# OvercurrentDetectionLogic.net
KiCad netlist of a schematic drawn in Altium Designer
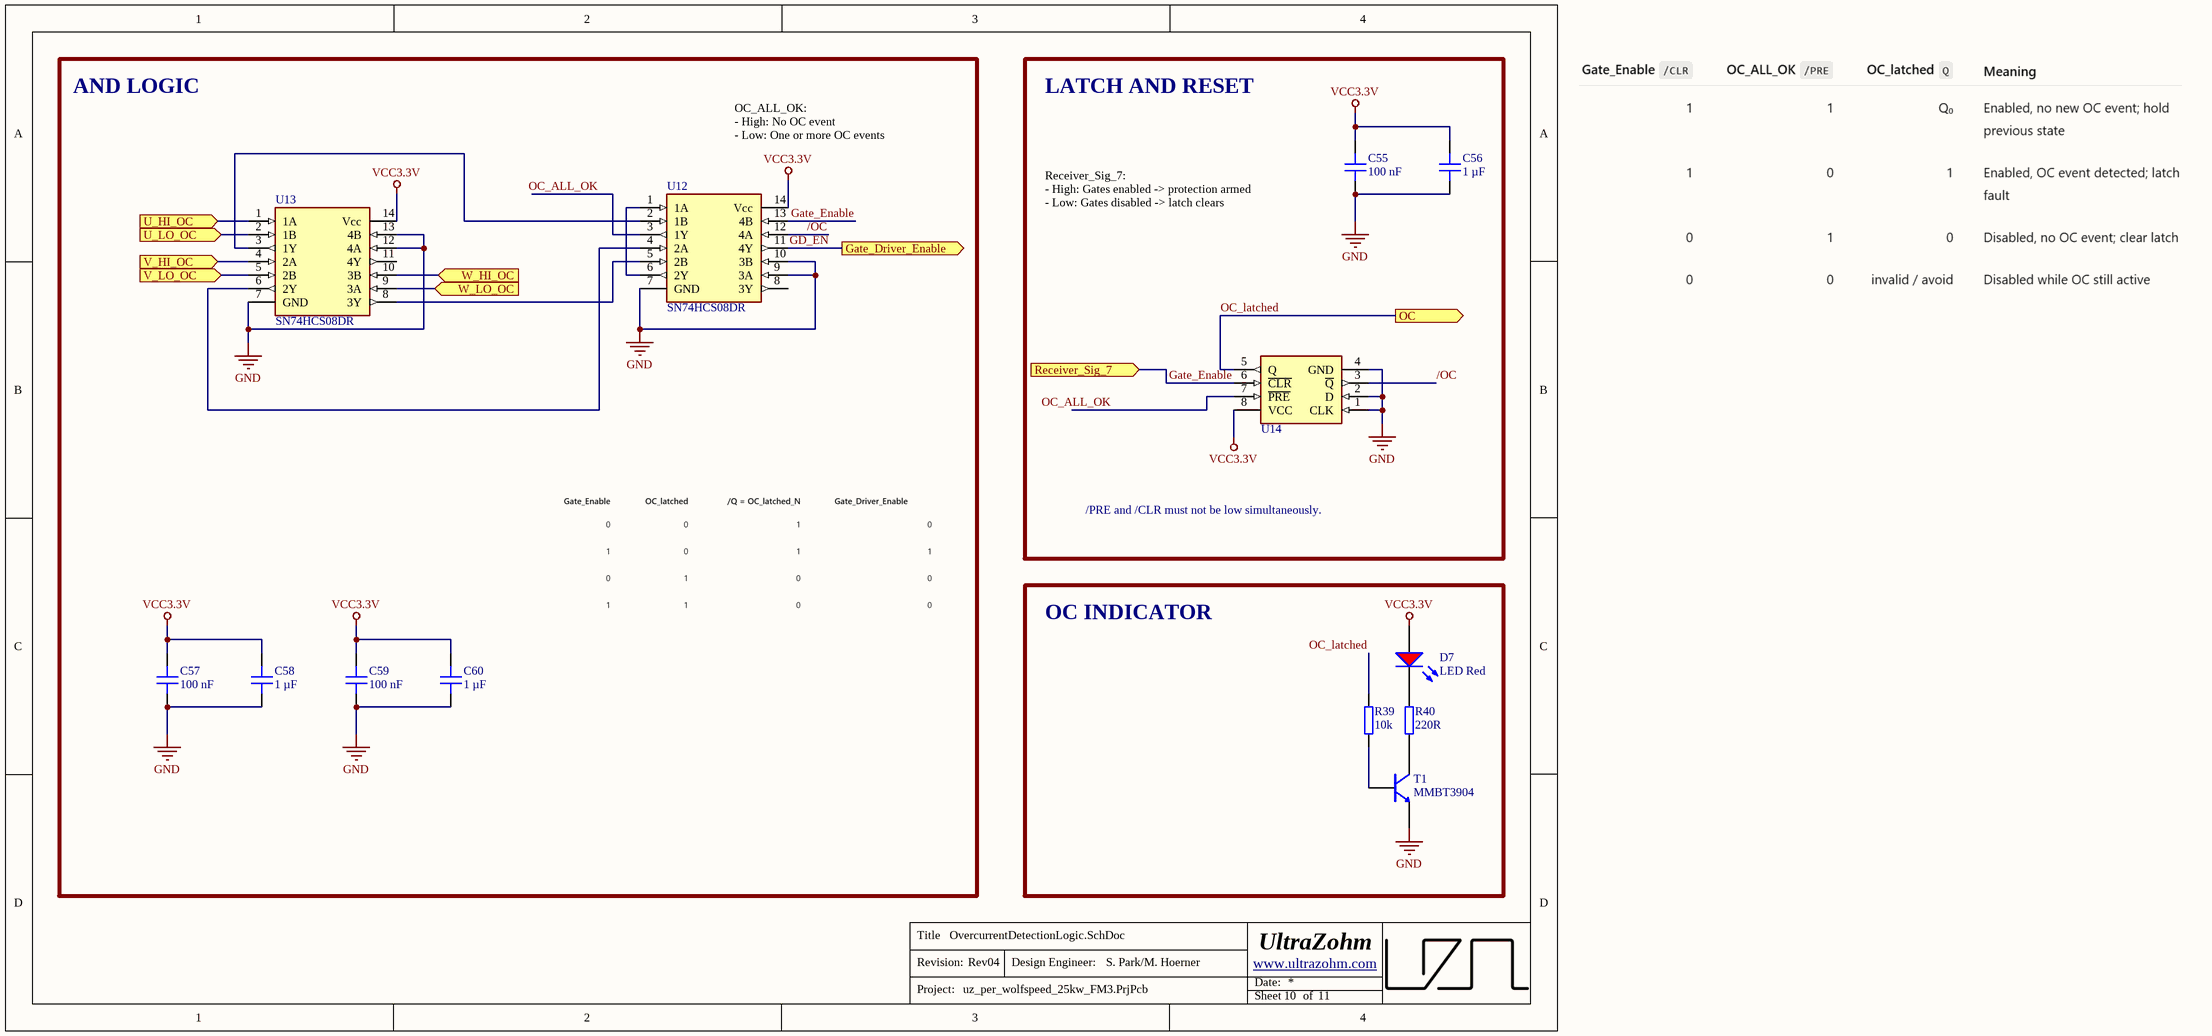
[diagram p0: OvercurrentDetectionLogic.SchDoc]

(export (version "E")
  (design (tool "Eeschema 10.0.6"))
  (components
    (comp (ref "C55")
      (value "100 nF")
      (footprint "C_0603")
      (description "Capacitor 0603, 50 VDC, 100nF, X7R")
      (fields
        (field (name "MANUFACTURER PART NUMBER") "C0603C104K5RAC3121")
        (field (name "MANUFACTURER") "KEMET")
        (field (name "CREATED FROM") "DHufnagel")
      )
      (libsource (lib "user") (part "Capacitor"))
    )
    (comp (ref "C56")
      (value "1 µF")
      (footprint "C_0603")
      (description "Capacitor 0603, 25 VDC, 1 µF, X7R")
      (fields
        (field (name "MANUFACTURER PART NUMBER") "C0603C105K3RAC7411")
        (field (name "MANUFACTURER") "KEMET")
        (field (name "CREATED FROM") "MGremer")
      )
      (libsource (lib "user") (part "Capacitor"))
    )
    (comp (ref "C57")
      (value "100 nF")
      (footprint "C_0603")
      (description "Capacitor 0603, 50 VDC, 100nF, X7R")
      (fields
        (field (name "MANUFACTURER PART NUMBER") "C0603C104K5RAC3121")
        (field (name "MANUFACTURER") "KEMET")
        (field (name "CREATED FROM") "DHufnagel")
      )
      (libsource (lib "user") (part "Capacitor"))
    )
    (comp (ref "C58")
      (value "1 µF")
      (footprint "C_0603")
      (description "Capacitor 0603, 25 VDC, 1 µF, X7R")
      (fields
        (field (name "MANUFACTURER PART NUMBER") "C0603C105K3RAC7411")
        (field (name "MANUFACTURER") "KEMET")
        (field (name "CREATED FROM") "MGremer")
      )
      (libsource (lib "user") (part "Capacitor"))
    )
    (comp (ref "C59")
      (value "100 nF")
      (footprint "C_0603")
      (description "Capacitor 0603, 50 VDC, 100nF, X7R")
      (fields
        (field (name "MANUFACTURER PART NUMBER") "C0603C104K5RAC3121")
        (field (name "MANUFACTURER") "KEMET")
        (field (name "CREATED FROM") "DHufnagel")
      )
      (libsource (lib "user") (part "Capacitor"))
    )
    (comp (ref "C60")
      (value "1 µF")
      (footprint "C_0603")
      (description "Capacitor 0603, 25 VDC, 1 µF, X7R")
      (fields
        (field (name "MANUFACTURER PART NUMBER") "C0603C105K3RAC7411")
        (field (name "MANUFACTURER") "KEMET")
        (field (name "CREATED FROM") "MGremer")
      )
      (libsource (lib "user") (part "Capacitor"))
    )
    (comp (ref "D7")
      (value "LED Red")
      (footprint "LEDM2012X80N")
      (description "Standard LEDs - SMD 0805 red")
      (fields
        (field (name "MANUFACTURER PART NUMBER") "UZgen_LED_0805_Red")
        (field (name "MANUFACTURER") "UZgen")
        (field (name "CREATED FROM") "UZgenTool")
      )
      (libsource (lib "user") (part "LED_Red"))
    )
    (comp (ref "R39")
      (value "10k")
      (footprint "RES 0603_1608")
      (description "SMD resistor E24 series")
      (fields
        (field (name "MANUFACTURER PART NUMBER") "RK73B1JTTD103J")
        (field (name "MANUFACTURER") "KOA Speer")
        (field (name "CREATED FROM") "MGremer")
      )
      (libsource (lib "user") (part "Resistor"))
    )
    (comp (ref "R40")
      (value "220R")
      (footprint "RES 0603_1608")
      (description "SMD resistor E24 series")
      (fields
        (field (name "MANUFACTURER PART NUMBER") "RK73B1JTTDD221J")
        (field (name "MANUFACTURER") "KOA Speer")
        (field (name "CREATED FROM") "MGremer")
      )
      (libsource (lib "user") (part "Resistor"))
    )
    (comp (ref "T1")
      (value "MMBT3904")
      (footprint "SOT95P280X145-3N")
      (fields
        (field (name "MANUFACTURER") "Jiangsu Changjing Electronics Technology Co., Ltd.")
        (field (name "LCSC PART NUMBER") "C20526")
        (field (name "CREATED FROM") "NDiringer")
      )
      (libsource (lib "user") (part "NPN-SOT23"))
    )
    (comp (ref "U12")
      (value "SN74HCS08DR")
      (footprint "SOIC127P600X175-14N")
      (description "Logische Gatter 4-ch 2-input 2-V to 6-V high-speed")
      (fields
        (field (name "MANUFACTURER") "Texas Instruments")
        (field (name "LCSC PART NUMBER") "C2868021")
        (field (name "CREATED FROM") "FRosner")
      )
      (libsource (lib "user") (part "SN74HCS32PWR"))
    )
    (comp (ref "U13")
      (value "SN74HCS08DR")
      (footprint "SOIC127P600X175-14N")
      (description "Logische Gatter 4-ch 2-input 2-V to 6-V high-speed")
      (fields
        (field (name "MANUFACTURER") "Texas Instruments")
        (field (name "LCSC PART NUMBER") "C2868021")
        (field (name "CREATED FROM") "FRosner")
      )
      (libsource (lib "user") (part "SN74HCS32PWR"))
    )
    (comp (ref "U14")
      (value "SN74LVC1G74DCTR")
      (footprint "MSOP-8")
      (description "Single Positive-Edge-Triggered D-Type Flip-Flop with Clear and Preset")
      (fields
        (field (name "MANUFACTURER") "Texas Instruments")
        (field (name "LCSC PART NUMBER") "C840104")
        (field (name "CREATED FROM") "FRosner")
      )
      (libsource (lib "user") (part "SN74LVC1G74DCTR"))
    )
  )
  (nets
    (net (code "1") (name "/GD_EN") (class "Default")
      (node (ref "U12") (pin "11") (pinfunction "4Y_11") (pintype "output"))
    )
    (net (code "2") (name "/Gate_Enable") (class "Default")
      (node (ref "U12") (pin "13") (pinfunction "4B_13") (pintype "input"))
      (node (ref "U14") (pin "6") (pinfunction "~{CLR}_6") (pintype "input"))
    )
    (net (code "3") (name "/OC_ALL_OK") (class "Default")
      (node (ref "U12") (pin "3") (pinfunction "1Y_3") (pintype "output"))
      (node (ref "U14") (pin "7") (pinfunction "~{PRE}_7") (pintype "input"))
    )
    (net (code "4") (name "/OC_latched") (class "Default")
      (node (ref "R39") (pin "2") (pinfunction "2_2") (pintype "passive"))
      (node (ref "U14") (pin "5") (pinfunction "Q_5") (pintype "output"))
    )
    (net (code "5") (name "/U_HI_OC") (class "Default")
      (node (ref "U13") (pin "1") (pinfunction "1A_1") (pintype "input"))
    )
    (net (code "6") (name "/U_LO_OC") (class "Default")
      (node (ref "U13") (pin "2") (pinfunction "1B_2") (pintype "input"))
    )
    (net (code "7") (name "/V_HI_OC") (class "Default")
      (node (ref "U13") (pin "4") (pinfunction "2A_4") (pintype "input"))
    )
    (net (code "8") (name "/V_LO_OC") (class "Default")
      (node (ref "U13") (pin "5") (pinfunction "2B_5") (pintype "input"))
    )
    (net (code "9") (name "/W_HI_OC") (class "Default")
      (node (ref "U13") (pin "10") (pinfunction "3B_10") (pintype "input"))
    )
    (net (code "10") (name "/W_LO_OC") (class "Default")
      (node (ref "U13") (pin "9") (pinfunction "3A_9") (pintype "input"))
    )
    (net (code "11") (name "/{slash}OC") (class "Default")
      (node (ref "U12") (pin "12") (pinfunction "4A_12") (pintype "input"))
      (node (ref "U14") (pin "3") (pinfunction "~{Q}_3") (pintype "output"))
    )
    (net (code "12") (name "GND") (class "Default")
      (node (ref "C55") (pin "2") (pinfunction "2_2") (pintype "passive"))
      (node (ref "C56") (pin "2") (pinfunction "2_2") (pintype "passive"))
      (node (ref "C57") (pin "2") (pinfunction "2_2") (pintype "passive"))
      (node (ref "C58") (pin "2") (pinfunction "2_2") (pintype "passive"))
      (node (ref "C59") (pin "2") (pinfunction "2_2") (pintype "passive"))
      (node (ref "C60") (pin "2") (pinfunction "2_2") (pintype "passive"))
      (node (ref "T1") (pin "2") (pinfunction "EMITTER_2") (pintype "passive"))
      (node (ref "U12") (pin "10") (pinfunction "3B_10") (pintype "input"))
      (node (ref "U12") (pin "7") (pinfunction "GND_7") (pintype "passive"))
      (node (ref "U12") (pin "9") (pinfunction "3A_9") (pintype "input"))
      (node (ref "U13") (pin "12") (pinfunction "4A_12") (pintype "input"))
      (node (ref "U13") (pin "13") (pinfunction "4B_13") (pintype "input"))
      (node (ref "U13") (pin "7") (pinfunction "GND_7") (pintype "passive"))
      (node (ref "U14") (pin "1") (pinfunction "CLK_1") (pintype "input"))
      (node (ref "U14") (pin "2") (pinfunction "D_2") (pintype "input"))
      (node (ref "U14") (pin "4") (pinfunction "GND_4") (pintype "power_in"))
    )
    (net (code "13") (name "Net-(D7-K)") (class "Default")
      (node (ref "D7") (pin "1") (pinfunction "K_1") (pintype "passive"))
      (node (ref "R40") (pin "2") (pinfunction "2_2") (pintype "passive"))
    )
    (net (code "14") (name "Net-(T1-BASIS)") (class "Default")
      (node (ref "R39") (pin "1") (pinfunction "1_1") (pintype "passive"))
      (node (ref "T1") (pin "1") (pinfunction "BASIS_1") (pintype "passive"))
    )
    (net (code "15") (name "Net-(T1-COLLECTOR)") (class "Default")
      (node (ref "R40") (pin "1") (pinfunction "1_1") (pintype "passive"))
      (node (ref "T1") (pin "3") (pinfunction "COLLECTOR_3") (pintype "passive"))
    )
    (net (code "16") (name "Net-(U12-1A)") (class "Default")
      (node (ref "U12") (pin "1") (pinfunction "1A_1") (pintype "input"))
      (node (ref "U12") (pin "6") (pinfunction "2Y_6") (pintype "output"))
    )
    (net (code "17") (name "Net-(U12-1B)") (class "Default")
      (node (ref "U12") (pin "2") (pinfunction "1B_2") (pintype "input"))
      (node (ref "U13") (pin "3") (pinfunction "1Y_3") (pintype "output"))
    )
    (net (code "18") (name "Net-(U12-2A)") (class "Default")
      (node (ref "U12") (pin "4") (pinfunction "2A_4") (pintype "input"))
      (node (ref "U13") (pin "6") (pinfunction "2Y_6") (pintype "output"))
    )
    (net (code "19") (name "Net-(U12-2B)") (class "Default")
      (node (ref "U12") (pin "5") (pinfunction "2B_5") (pintype "input"))
      (node (ref "U13") (pin "8") (pinfunction "3Y_8") (pintype "output"))
    )
    (net (code "20") (name "VCC3.3V") (class "Default")
      (node (ref "C55") (pin "1") (pinfunction "1_1") (pintype "passive"))
      (node (ref "C56") (pin "1") (pinfunction "1_1") (pintype "passive"))
      (node (ref "C57") (pin "1") (pinfunction "1_1") (pintype "passive"))
      (node (ref "C58") (pin "1") (pinfunction "1_1") (pintype "passive"))
      (node (ref "C59") (pin "1") (pinfunction "1_1") (pintype "passive"))
      (node (ref "C60") (pin "1") (pinfunction "1_1") (pintype "passive"))
      (node (ref "D7") (pin "2") (pinfunction "A_2") (pintype "passive"))
      (node (ref "U12") (pin "14") (pinfunction "Vcc_14") (pintype "passive"))
      (node (ref "U13") (pin "14") (pinfunction "Vcc_14") (pintype "passive"))
      (node (ref "U14") (pin "8") (pinfunction "VCC_8") (pintype "power_in"))
    )
    (net (code "21") (name "unconnected-(U12-3Y-Pad8)") (class "Default")
      (node (ref "U12") (pin "8") (pinfunction "3Y_8") (pintype "output"))
    )
    (net (code "22") (name "unconnected-(U13-4Y-Pad11)") (class "Default")
      (node (ref "U13") (pin "11") (pinfunction "4Y_11") (pintype "output"))
    )
  )
)
